# MaTouch_ESP32-S3_2_13_Quad-Color_Eink_V1.net
KiCad netlist of a schematic drawn in EAGLE
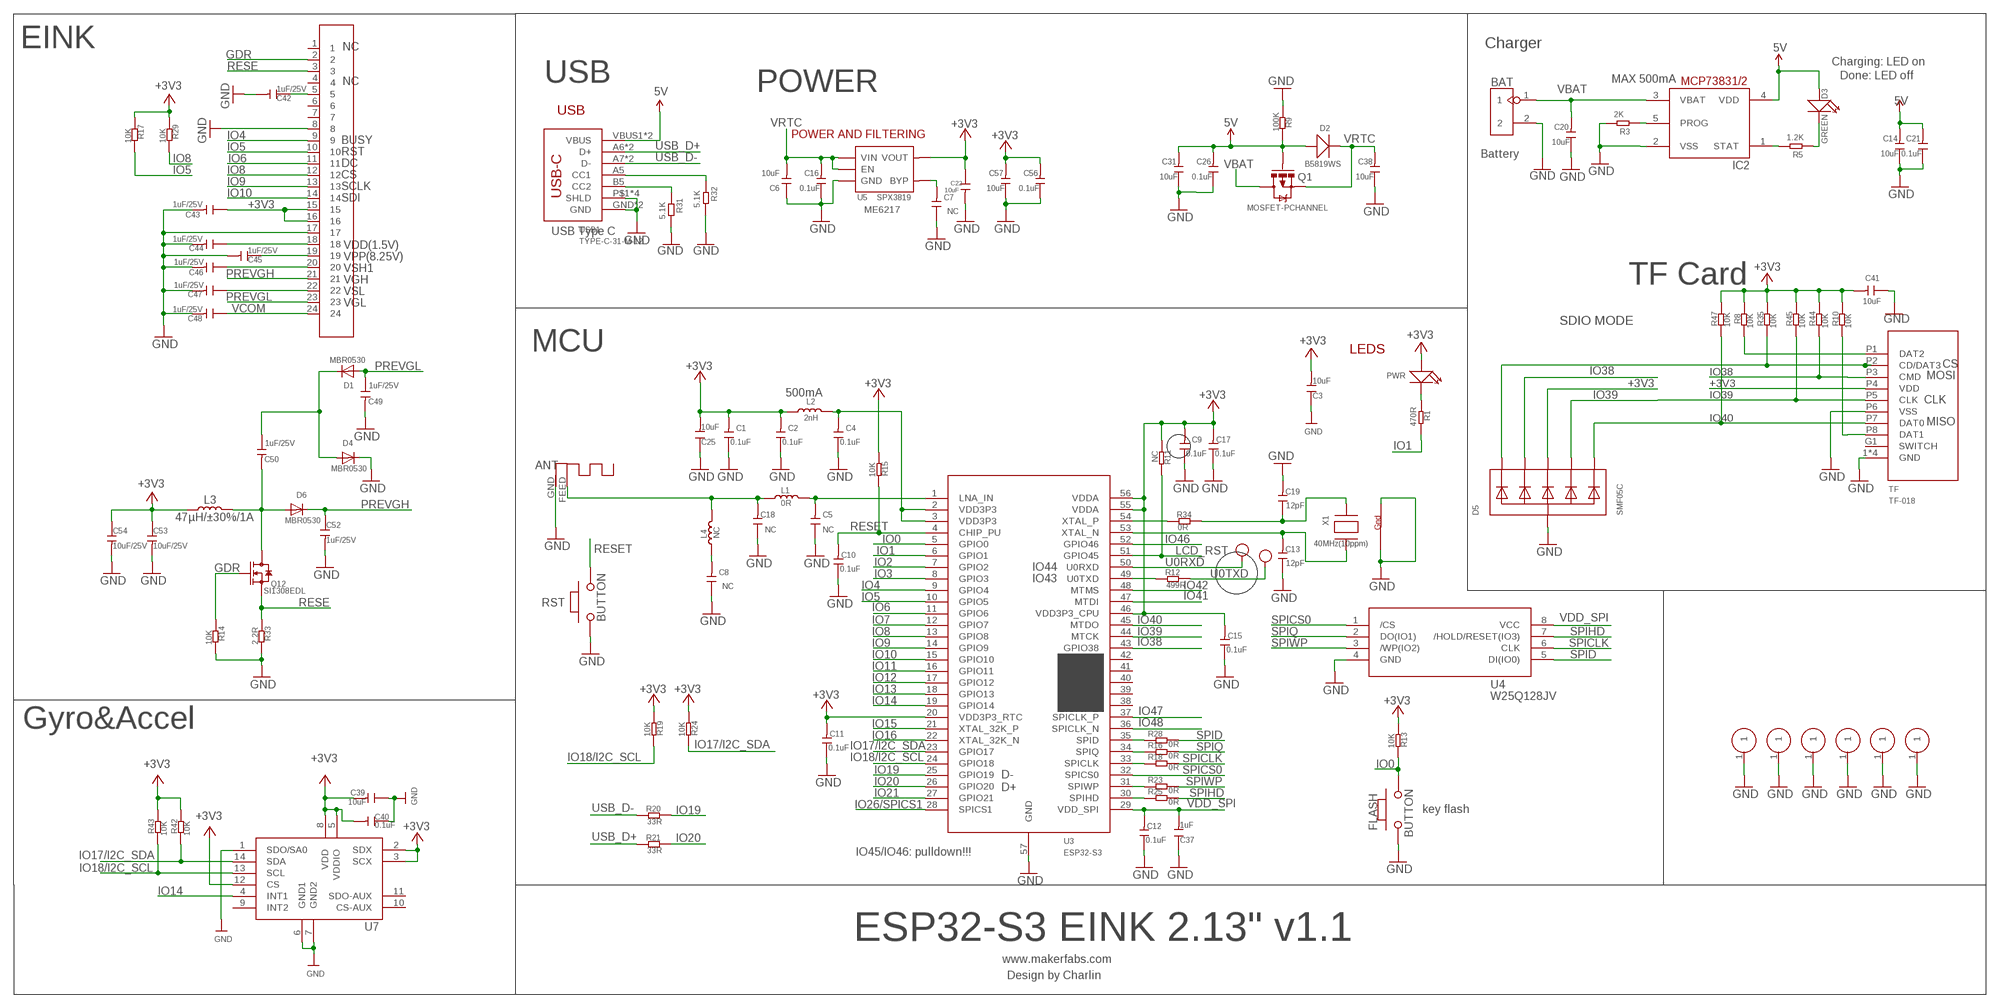
[diagram p0: schematic, sheet 1]

(export (version "E")
  (design (tool "Eeschema 10.0.6"))
  (components
    (comp (ref "ANT1")
      (value "ANTENNA")
      (footprint "eagle-import:RN-ANT")
      (libsource (lib "eagle-import") (part "ANTENNA"))
    )
    (comp (ref "BAT")
      (value "HEADER-2P-2.0")
      (footprint "eagle-import:2P-2.0")
      (libsource (lib "eagle-import") (part "HEADER-2P-2.0"))
    )
    (comp (ref "C1")
      (value "0.1uF")
      (footprint "eagle-import:DISCRETE_C0402")
      (libsource (lib "eagle-import") (part "DISCRETE_C-0402"))
    )
    (comp (ref "C2")
      (value "0.1uF")
      (footprint "eagle-import:DISCRETE_C0402")
      (libsource (lib "eagle-import") (part "DISCRETE_C-0402"))
    )
    (comp (ref "C3")
      (value "10uF")
      (footprint "eagle-import:DISCRETE_C0603")
      (libsource (lib "eagle-import") (part "DISCRETE_C-0603"))
    )
    (comp (ref "C4")
      (value "0.1uF")
      (footprint "eagle-import:DISCRETE_C0402")
      (libsource (lib "eagle-import") (part "DISCRETE_C-0402"))
    )
    (comp (ref "C5")
      (value "NC")
      (footprint "eagle-import:DISCRETE_C0402")
      (libsource (lib "eagle-import") (part "DISCRETE_C-0402"))
    )
    (comp (ref "C6")
      (value "10uF")
      (footprint "eagle-import:DISCRETE_C0603")
      (libsource (lib "eagle-import") (part "DISCRETE_C-0603"))
    )
    (comp (ref "C7")
      (value "NC")
      (footprint "eagle-import:DISCRETE_C0402")
      (libsource (lib "eagle-import") (part "DISCRETE_C-0402"))
    )
    (comp (ref "C8")
      (value "NC")
      (footprint "eagle-import:DISCRETE_C0402")
      (libsource (lib "eagle-import") (part "DISCRETE_C-0402"))
    )
    (comp (ref "C9")
      (value "0.1uF")
      (footprint "eagle-import:DISCRETE_C0402")
      (libsource (lib "eagle-import") (part "DISCRETE_C-0402"))
    )
    (comp (ref "C10")
      (value "0.1uF")
      (footprint "eagle-import:DISCRETE_C0402")
      (libsource (lib "eagle-import") (part "DISCRETE_C-0402"))
    )
    (comp (ref "C11")
      (value "0.1uF")
      (footprint "eagle-import:DISCRETE_C0402")
      (libsource (lib "eagle-import") (part "DISCRETE_C-0402"))
    )
    (comp (ref "C12")
      (value "0.1uF")
      (footprint "eagle-import:DISCRETE_C0402")
      (libsource (lib "eagle-import") (part "DISCRETE_C-0402"))
    )
    (comp (ref "C13")
      (value "12pF")
      (footprint "eagle-import:DISCRETE_C0402")
      (libsource (lib "eagle-import") (part "DISCRETE_C-0402"))
    )
    (comp (ref "C14")
      (value "10uF")
      (footprint "eagle-import:DISCRETE_C0402")
      (libsource (lib "eagle-import") (part "DISCRETE_C-0402"))
    )
    (comp (ref "C15")
      (value "0.1uF")
      (footprint "eagle-import:DISCRETE_C0402")
      (libsource (lib "eagle-import") (part "DISCRETE_C-0402"))
    )
    (comp (ref "C16")
      (value "0.1uF")
      (footprint "eagle-import:DISCRETE_C0402")
      (libsource (lib "eagle-import") (part "DISCRETE_C-0402"))
    )
    (comp (ref "C17")
      (value "0.1uF")
      (footprint "eagle-import:DISCRETE_C0402")
      (libsource (lib "eagle-import") (part "DISCRETE_C-0402"))
    )
    (comp (ref "C18")
      (value "NC")
      (footprint "eagle-import:DISCRETE_C0402")
      (libsource (lib "eagle-import") (part "DISCRETE_C-0402"))
    )
    (comp (ref "C19")
      (value "12pF")
      (footprint "eagle-import:DISCRETE_C0402")
      (libsource (lib "eagle-import") (part "DISCRETE_C-0402"))
    )
    (comp (ref "C20")
      (value "10uF")
      (footprint "eagle-import:DISCRETE_C0402")
      (libsource (lib "eagle-import") (part "DISCRETE_C-0402"))
    )
    (comp (ref "C21")
      (value "0.1uF")
      (footprint "eagle-import:DISCRETE_C0402")
      (libsource (lib "eagle-import") (part "DISCRETE_C-0402"))
    )
    (comp (ref "C22")
      (value "10uF")
      (footprint "eagle-import:0603")
      (libsource (lib "eagle-import") (part "C-0603"))
    )
    (comp (ref "C25")
      (value "10uF")
      (footprint "eagle-import:DISCRETE_C0603")
      (libsource (lib "eagle-import") (part "DISCRETE_C-0603"))
    )
    (comp (ref "C26")
      (value "0.1uF")
      (footprint "eagle-import:DISCRETE_C0402")
      (libsource (lib "eagle-import") (part "DISCRETE_C-0402"))
    )
    (comp (ref "C31")
      (value "10uF")
      (footprint "eagle-import:DISCRETE_C0402")
      (libsource (lib "eagle-import") (part "DISCRETE_C-0402"))
    )
    (comp (ref "C37")
      (value "1uF")
      (footprint "eagle-import:DISCRETE_C0603")
      (libsource (lib "eagle-import") (part "DISCRETE_C-0603"))
    )
    (comp (ref "C38")
      (value "10uF")
      (footprint "eagle-import:DISCRETE_C0402")
      (libsource (lib "eagle-import") (part "DISCRETE_C-0402"))
    )
    (comp (ref "C39")
      (value "10uF")
      (footprint "eagle-import:DISCRETE_C0402")
      (libsource (lib "eagle-import") (part "DISCRETE_C-0402"))
    )
    (comp (ref "C40")
      (value "0.1uF")
      (footprint "eagle-import:DISCRETE_C0402")
      (libsource (lib "eagle-import") (part "DISCRETE_C-0402"))
    )
    (comp (ref "C41")
      (value "10uF")
      (footprint "eagle-import:DISCRETE_C0402")
      (libsource (lib "eagle-import") (part "DISCRETE_C-0402"))
    )
    (comp (ref "C42")
      (value "1uF/25V")
      (footprint "eagle-import:DISCRETE_C0402")
      (libsource (lib "eagle-import") (part "DISCRETE_C-0402"))
    )
    (comp (ref "C43")
      (value "1uF/25V")
      (footprint "eagle-import:DISCRETE_C0402")
      (libsource (lib "eagle-import") (part "DISCRETE_C-0402"))
    )
    (comp (ref "C44")
      (value "1uF/25V")
      (footprint "eagle-import:DISCRETE_C0402")
      (libsource (lib "eagle-import") (part "DISCRETE_C-0402"))
    )
    (comp (ref "C45")
      (value "1uF/25V")
      (footprint "eagle-import:DISCRETE_C0402")
      (libsource (lib "eagle-import") (part "DISCRETE_C-0402"))
    )
    (comp (ref "C46")
      (value "1uF/25V")
      (footprint "eagle-import:DISCRETE_C0402")
      (libsource (lib "eagle-import") (part "DISCRETE_C-0402"))
    )
    (comp (ref "C47")
      (value "1uF/25V")
      (footprint "eagle-import:DISCRETE_C0402")
      (libsource (lib "eagle-import") (part "DISCRETE_C-0402"))
    )
    (comp (ref "C48")
      (value "1uF/25V")
      (footprint "eagle-import:DISCRETE_C0402")
      (libsource (lib "eagle-import") (part "DISCRETE_C-0402"))
    )
    (comp (ref "C49")
      (value "1uF/25V")
      (footprint "eagle-import:DISCRETE_C0402")
      (libsource (lib "eagle-import") (part "DISCRETE_C-0402"))
    )
    (comp (ref "C50")
      (value "1uF/25V")
      (footprint "eagle-import:DISCRETE_C0402")
      (libsource (lib "eagle-import") (part "DISCRETE_C-0402"))
    )
    (comp (ref "C52")
      (value "1uF/25V")
      (footprint "eagle-import:0603")
      (libsource (lib "eagle-import") (part "C-0603"))
    )
    (comp (ref "C53")
      (value "10uF/25V")
      (footprint "eagle-import:0603")
      (libsource (lib "eagle-import") (part "C-0603"))
    )
    (comp (ref "C54")
      (value "10uF/25V")
      (footprint "eagle-import:0603")
      (libsource (lib "eagle-import") (part "C-0603"))
    )
    (comp (ref "C56")
      (value "0.1uF")
      (footprint "eagle-import:DISCRETE_C0402")
      (libsource (lib "eagle-import") (part "DISCRETE_C-0402"))
    )
    (comp (ref "C57")
      (value "10uF")
      (footprint "eagle-import:DISCRETE_C0402")
      (libsource (lib "eagle-import") (part "DISCRETE_C-0402"))
    )
    (comp (ref "D1")
      (value "MBR0530")
      (footprint "eagle-import:SOD-323F")
      (libsource (lib "eagle-import") (part "DIODESOD-323F"))
    )
    (comp (ref "D2")
      (value "B5819WS")
      (footprint "eagle-import:SOD323")
      (libsource (lib "eagle-import") (part "D'0805'"))
    )
    (comp (ref "D3")
      (value "GREEN")
      (footprint "eagle-import:DISCRETE_LED-0603")
      (libsource (lib "eagle-import") (part "DISCRETE_LED0603"))
    )
    (comp (ref "D4")
      (value "MBR0530")
      (footprint "eagle-import:SOD-323F")
      (libsource (lib "eagle-import") (part "DIODESOD-323F"))
    )
    (comp (ref "D5")
      (value "SMF05C")
      (footprint "eagle-import:SOT363")
      (libsource (lib "eagle-import") (part "TVSARRAY_5LANE"))
    )
    (comp (ref "D6")
      (value "MBR0530")
      (footprint "eagle-import:SOD-323F")
      (libsource (lib "eagle-import") (part "DIODESOD-323F"))
    )
    (comp (ref "FLASH")
      (value "BUTTON")
      (footprint "eagle-import:157SW")
      (libsource (lib "eagle-import") (part "PB157"))
    )
    (comp (ref "IC2")
      (value "TP4054")
      (footprint "eagle-import:SOT23-5L")
      (libsource (lib "eagle-import") (part "MCP73831/OT"))
    )
    (comp (ref "J1")
      (value "FPC24-80P-A")
      (footprint "eagle-import:SMD24-80P-1960L440W")
      (libsource (lib "eagle-import") (part "FPC24-80P-A"))
    )
    (comp (ref "L1")
      (value "0R")
      (footprint "eagle-import:DISCRETE_L0402")
      (libsource (lib "eagle-import") (part "DISCRETE_L0402"))
    )
    (comp (ref "L2")
      (value "2nH")
      (footprint "eagle-import:DISCRETE_L0603")
      (libsource (lib "eagle-import") (part "DISCRETE_L0603"))
    )
    (comp (ref "L3")
      (value "47µH/±30%/1A")
      (footprint "eagle-import:CR54")
      (fields (field (name "PROD_ID") "NDUC-10789"))
      (libsource (lib "eagle-import") (part "INDUCTOR-CR54-47UH"))
    )
    (comp (ref "L4")
      (value "NC")
      (footprint "eagle-import:DISCRETE_L0402")
      (libsource (lib "eagle-import") (part "DISCRETE_L0402"))
    )
    (comp (ref "PWR")
      (value "DISCRETE_LED0603")
      (footprint "eagle-import:DISCRETE_LED-0603")
      (libsource (lib "eagle-import") (part "DISCRETE_LED0603"))
    )
    (comp (ref "Q1")
      (value "MOSFET-PCHANNEL")
      (footprint "eagle-import:SOT23-3")
      (libsource (lib "eagle-import") (part "MOSFET-PCHANNEL"))
    )
    (comp (ref "Q12")
      (value "SI1308EDL")
      (footprint "eagle-import:SOT23")
      (libsource (lib "eagle-import") (part "MOSFET-N'SOT23'"))
    )
    (comp (ref "R1")
      (value "470R")
      (footprint "eagle-import:DISCRETE_R0402")
      (libsource (lib "eagle-import") (part "DISCRETE_R-0402"))
    )
    (comp (ref "R3")
      (value "2K")
      (footprint "eagle-import:DISCRETE_R0402")
      (libsource (lib "eagle-import") (part "DISCRETE_R-0402"))
    )
    (comp (ref "R5")
      (value "1.2K")
      (footprint "eagle-import:DISCRETE_R0402")
      (libsource (lib "eagle-import") (part "DISCRETE_R-0402"))
    )
    (comp (ref "R8")
      (value "10K")
      (footprint "eagle-import:DISCRETE_R0402")
      (libsource (lib "eagle-import") (part "DISCRETE_R-0402"))
    )
    (comp (ref "R9")
      (value "100K")
      (footprint "eagle-import:DISCRETE_R0402")
      (libsource (lib "eagle-import") (part "DISCRETE_R-0402"))
    )
    (comp (ref "R10")
      (value "10K")
      (footprint "eagle-import:DISCRETE_R0402")
      (libsource (lib "eagle-import") (part "DISCRETE_R-0402"))
    )
    (comp (ref "R11")
      (value "NC")
      (footprint "eagle-import:DISCRETE_R0402")
      (libsource (lib "eagle-import") (part "DISCRETE_R-0402"))
    )
    (comp (ref "R12")
      (value "499R")
      (footprint "eagle-import:DISCRETE_R0402")
      (libsource (lib "eagle-import") (part "DISCRETE_R-0402"))
    )
    (comp (ref "R13")
      (value "10K")
      (footprint "eagle-import:DISCRETE_R0402")
      (libsource (lib "eagle-import") (part "DISCRETE_R-0402"))
    )
    (comp (ref "R14")
      (value "10K")
      (footprint "eagle-import:DISCRETE_R0402")
      (libsource (lib "eagle-import") (part "DISCRETE_R-0402"))
    )
    (comp (ref "R15")
      (value "10K")
      (footprint "eagle-import:DISCRETE_R0402")
      (libsource (lib "eagle-import") (part "DISCRETE_R-0402"))
    )
    (comp (ref "R16")
      (value "0R")
      (footprint "eagle-import:DISCRETE_R0402")
      (libsource (lib "eagle-import") (part "DISCRETE_R-0402"))
    )
    (comp (ref "R17")
      (value "10K")
      (footprint "eagle-import:DISCRETE_R0402")
      (libsource (lib "eagle-import") (part "DISCRETE_R-0402"))
    )
    (comp (ref "R18")
      (value "0R")
      (footprint "eagle-import:DISCRETE_R0402")
      (libsource (lib "eagle-import") (part "DISCRETE_R-0402"))
    )
    (comp (ref "R19")
      (value "10K")
      (footprint "eagle-import:DISCRETE_R0402")
      (libsource (lib "eagle-import") (part "DISCRETE_R-0402"))
    )
    (comp (ref "R20")
      (value "33R")
      (footprint "eagle-import:DISCRETE_R0402")
      (libsource (lib "eagle-import") (part "DISCRETE_R-0402"))
    )
    (comp (ref "R21")
      (value "33R")
      (footprint "eagle-import:DISCRETE_R0402")
      (libsource (lib "eagle-import") (part "DISCRETE_R-0402"))
    )
    (comp (ref "R23")
      (value "0R")
      (footprint "eagle-import:DISCRETE_R0402")
      (libsource (lib "eagle-import") (part "DISCRETE_R-0402"))
    )
    (comp (ref "R24")
      (value "10K")
      (footprint "eagle-import:DISCRETE_R0402")
      (libsource (lib "eagle-import") (part "DISCRETE_R-0402"))
    )
    (comp (ref "R25")
      (value "0R")
      (footprint "eagle-import:DISCRETE_R0402")
      (libsource (lib "eagle-import") (part "DISCRETE_R-0402"))
    )
    (comp (ref "R28")
      (value "0R")
      (footprint "eagle-import:DISCRETE_R0402")
      (libsource (lib "eagle-import") (part "DISCRETE_R-0402"))
    )
    (comp (ref "R29")
      (value "10K")
      (footprint "eagle-import:DISCRETE_R0402")
      (libsource (lib "eagle-import") (part "DISCRETE_R-0402"))
    )
    (comp (ref "R31")
      (value "5.1K")
      (footprint "eagle-import:DISCRETE_R0402")
      (libsource (lib "eagle-import") (part "DISCRETE_R-0402"))
    )
    (comp (ref "R32")
      (value "5.1K")
      (footprint "eagle-import:DISCRETE_R0402")
      (libsource (lib "eagle-import") (part "DISCRETE_R-0402"))
    )
    (comp (ref "R33")
      (value "2.2R")
      (footprint "eagle-import:DISCRETE_R0402")
      (libsource (lib "eagle-import") (part "DISCRETE_R-0402"))
    )
    (comp (ref "R34")
      (value "0R")
      (footprint "eagle-import:DISCRETE_R0402")
      (libsource (lib "eagle-import") (part "DISCRETE_R-0402"))
    )
    (comp (ref "R35")
      (value "10K")
      (footprint "eagle-import:DISCRETE_R0402")
      (libsource (lib "eagle-import") (part "DISCRETE_R-0402"))
    )
    (comp (ref "R42")
      (value "10K")
      (footprint "eagle-import:DISCRETE_R0402")
      (libsource (lib "eagle-import") (part "DISCRETE_R-0402"))
    )
    (comp (ref "R43")
      (value "10K")
      (footprint "eagle-import:DISCRETE_R0402")
      (libsource (lib "eagle-import") (part "DISCRETE_R-0402"))
    )
    (comp (ref "R44")
      (value "10K")
      (footprint "eagle-import:DISCRETE_R0402")
      (libsource (lib "eagle-import") (part "DISCRETE_R-0402"))
    )
    (comp (ref "R45")
      (value "10K")
      (footprint "eagle-import:DISCRETE_R0402")
      (libsource (lib "eagle-import") (part "DISCRETE_R-0402"))
    )
    (comp (ref "R47")
      (value "10K")
      (footprint "eagle-import:DISCRETE_R0402")
      (libsource (lib "eagle-import") (part "DISCRETE_R-0402"))
    )
    (comp (ref "RST")
      (value "BUTTON")
      (footprint "eagle-import:157SW")
      (libsource (lib "eagle-import") (part "PB157"))
    )
    (comp (ref "RX")
      (value "TEST-POINT'4545'")
      (footprint "eagle-import:TP-D45MIL")
      (fields (field (name "PARTNO") "DNP") (field (name "PARTNO_1") "DNP"))
      (libsource (lib "eagle-import") (part "TEST-POINT'4545'"))
    )
    (comp (ref "S1")
      (value "ONEPIN01")
      (footprint "eagle-import:ONEPIN01")
      (libsource (lib "eagle-import") (part "ONEPIN01"))
    )
    (comp (ref "S2")
      (value "ONEPIN01")
      (footprint "eagle-import:ONEPIN01")
      (libsource (lib "eagle-import") (part "ONEPIN01"))
    )
    (comp (ref "S3")
      (value "ONEPIN01")
      (footprint "eagle-import:ONEPIN01")
      (libsource (lib "eagle-import") (part "ONEPIN01"))
    )
    (comp (ref "S4")
      (value "ONEPIN01")
      (footprint "eagle-import:ONEPIN01")
      (libsource (lib "eagle-import") (part "ONEPIN01"))
    )
    (comp (ref "S5")
      (value "ONEPIN01")
      (footprint "eagle-import:ONEPIN01")
      (libsource (lib "eagle-import") (part "ONEPIN01"))
    )
    (comp (ref "S6")
      (value "ONEPIN01")
      (footprint "eagle-import:ONEPIN01")
      (libsource (lib "eagle-import") (part "ONEPIN01"))
    )
    (comp (ref "TF")
      (value "TF-018")
      (footprint "eagle-import:TF-018")
      (libsource (lib "eagle-import") (part "TF-018"))
    )
    (comp (ref "TX")
      (value "TEST-POINT'4545'")
      (footprint "eagle-import:TP-D45MIL")
      (fields (field (name "PARTNO") "DNP") (field (name "PARTNO_1") "DNP"))
      (libsource (lib "eagle-import") (part "TEST-POINT'4545'"))
    )
    (comp (ref "U3")
      (value "ESP32-S3")
      (footprint "eagle-import:QFN56-7_7MM")
      (libsource (lib "eagle-import") (part "ESP32-S3"))
    )
    (comp (ref "U4")
      (value "W25Q128JV")
      (footprint "eagle-import:SOIC-8-208MIL")
      (libsource (lib "eagle-import") (part "W25Q128JV"))
    )
    (comp (ref "U5")
      (value "SPX3819")
      (footprint "eagle-import:SOT23-5")
      (libsource (lib "eagle-import") (part "SPX3819"))
    )
    (comp (ref "U7")
      (value "QMI8658A")
      (footprint "eagle-import:LGA14-50P-300L250W86H")
      (libsource (lib "eagle-import") (part "QMI8658A"))
    )
    (comp (ref "USB1")
      (value "TYPE-C-31-M-12")
      (footprint "eagle-import:TYPE-C-31-M-12")
      (libsource (lib "eagle-import") (part "TYPE-C-31-M-12"))
    )
    (comp (ref "X1")
      (value "40MHz(10ppm)")
      (footprint "eagle-import:NX3225")
      (libsource (lib "eagle-import") (part "XTAL-4-3225"))
    )
  )
  (nets
    (net (code "1") (name "+3V3") (class "Default")
      (node (ref "C1") (pin "2") (pinfunction "2_2") (pintype "passive"))
      (node (ref "C11") (pin "2") (pinfunction "2_2") (pintype "passive"))
      (node (ref "C15") (pin "2") (pinfunction "2_2") (pintype "passive"))
      (node (ref "C17") (pin "2") (pinfunction "2_2") (pintype "passive"))
      (node (ref "C2") (pin "2") (pinfunction "2_2") (pintype "passive"))
      (node (ref "C22") (pin "1") (pinfunction "1_1") (pintype "passive"))
      (node (ref "C25") (pin "2") (pinfunction "2_2") (pintype "passive"))
      (node (ref "C3") (pin "2") (pinfunction "2_2") (pintype "passive"))
      (node (ref "C39") (pin "2") (pinfunction "2_2") (pintype "passive"))
      (node (ref "C40") (pin "2") (pinfunction "2_2") (pintype "passive"))
      (node (ref "C41") (pin "2") (pinfunction "2_2") (pintype "passive"))
      (node (ref "C43") (pin "1") (pinfunction "1_1") (pintype "passive"))
      (node (ref "C53") (pin "1") (pinfunction "1_1") (pintype "passive"))
      (node (ref "C54") (pin "1") (pinfunction "1_1") (pintype "passive"))
      (node (ref "C56") (pin "2") (pinfunction "2_2") (pintype "passive"))
      (node (ref "C57") (pin "2") (pinfunction "2_2") (pintype "passive"))
      (node (ref "C9") (pin "2") (pinfunction "2_2") (pintype "passive"))
      (node (ref "D5") (pin "4") (pinfunction "C3_4") (pintype "passive"))
      (node (ref "J1") (pin "15") (pinfunction "15_15") (pintype "bidirectional"))
      (node (ref "J1") (pin "16") (pinfunction "16_16") (pintype "bidirectional"))
      (node (ref "L2") (pin "1") (pinfunction "1_1") (pintype "passive"))
      (node (ref "L3") (pin "P$1") (pinfunction "1_P$1") (pintype "passive"))
      (node (ref "PWR") (pin "+") (pinfunction "+_+") (pintype "passive"))
      (node (ref "R10") (pin "2") (pinfunction "2_2") (pintype "passive"))
      (node (ref "R11") (pin "2") (pinfunction "2_2") (pintype "passive"))
      (node (ref "R13") (pin "2") (pinfunction "2_2") (pintype "passive"))
      (node (ref "R15") (pin "2") (pinfunction "2_2") (pintype "passive"))
      (node (ref "R17") (pin "1") (pinfunction "1_1") (pintype "passive"))
      (node (ref "R19") (pin "2") (pinfunction "2_2") (pintype "passive"))
      (node (ref "R24") (pin "2") (pinfunction "2_2") (pintype "passive"))
      (node (ref "R29") (pin "1") (pinfunction "1_1") (pintype "passive"))
      (node (ref "R35") (pin "2") (pinfunction "2_2") (pintype "passive"))
      (node (ref "R42") (pin "2") (pinfunction "2_2") (pintype "passive"))
      (node (ref "R43") (pin "2") (pinfunction "2_2") (pintype "passive"))
      (node (ref "R44") (pin "2") (pinfunction "2_2") (pintype "passive"))
      (node (ref "R45") (pin "2") (pinfunction "2_2") (pintype "passive"))
      (node (ref "R47") (pin "2") (pinfunction "2_2") (pintype "passive"))
      (node (ref "R8") (pin "2") (pinfunction "2_2") (pintype "passive"))
      (node (ref "TF") (pin "P4") (pinfunction "VDD_P4") (pintype "bidirectional"))
      (node (ref "U3") (pin "20") (pinfunction "VDD3P3_RTC_20") (pintype "bidirectional"))
      (node (ref "U3") (pin "46") (pinfunction "VDD3P3_CPU_46") (pintype "bidirectional"))
      (node (ref "U3") (pin "55") (pinfunction "VDDA_55") (pintype "bidirectional"))
      (node (ref "U3") (pin "56") (pinfunction "VDDA_56") (pintype "bidirectional"))
      (node (ref "U5") (pin "5") (pinfunction "VOUT_5") (pintype "bidirectional"))
      (node (ref "U7") (pin "12") (pinfunction "CS_12") (pintype "bidirectional"))
      (node (ref "U7") (pin "2") (pinfunction "SDX_2") (pintype "bidirectional"))
      (node (ref "U7") (pin "3") (pinfunction "SCX_3") (pintype "bidirectional"))
      (node (ref "U7") (pin "5") (pinfunction "VDDIO_5") (pintype "bidirectional"))
      (node (ref "U7") (pin "8") (pinfunction "VDD_8") (pintype "bidirectional"))
    )
    (net (code "2") (name "/GDR") (class "Default")
      (node (ref "J1") (pin "2") (pinfunction "2_2") (pintype "bidirectional"))
      (node (ref "Q12") (pin "1") (pinfunction "G_1") (pintype "passive"))
      (node (ref "R14") (pin "1") (pinfunction "1_1") (pintype "passive"))
    )
    (net (code "3") (name "/IO0") (class "Default")
      (node (ref "FLASH") (pin "2") (pinfunction "2_2") (pintype "passive"))
      (node (ref "R13") (pin "1") (pinfunction "1_1") (pintype "passive"))
      (node (ref "U3") (pin "5") (pinfunction "GPIO0_5") (pintype "bidirectional"))
    )
    (net (code "4") (name "/IO1") (class "Default")
      (node (ref "R1") (pin "1") (pinfunction "1_1") (pintype "passive"))
      (node (ref "U3") (pin "6") (pinfunction "GPIO1_6") (pintype "bidirectional"))
    )
    (net (code "5") (name "/IO2") (class "Default")
      (node (ref "U3") (pin "7") (pinfunction "GPIO2_7") (pintype "bidirectional"))
    )
    (net (code "6") (name "/IO3") (class "Default")
      (node (ref "U3") (pin "8") (pinfunction "GPIO3_8") (pintype "bidirectional"))
    )
    (net (code "7") (name "/IO4") (class "Default")
      (node (ref "J1") (pin "9") (pinfunction "9_9") (pintype "bidirectional"))
      (node (ref "U3") (pin "9") (pinfunction "GPIO4_9") (pintype "bidirectional"))
    )
    (net (code "8") (name "/IO5") (class "Default")
      (node (ref "J1") (pin "10") (pinfunction "10_10") (pintype "bidirectional"))
      (node (ref "R17") (pin "2") (pinfunction "2_2") (pintype "passive"))
      (node (ref "U3") (pin "10") (pinfunction "GPIO5_10") (pintype "bidirectional"))
    )
    (net (code "9") (name "/IO6") (class "Default")
      (node (ref "J1") (pin "11") (pinfunction "11_11") (pintype "bidirectional"))
      (node (ref "U3") (pin "11") (pinfunction "GPIO6_11") (pintype "bidirectional"))
    )
    (net (code "10") (name "/IO7") (class "Default")
      (node (ref "U3") (pin "12") (pinfunction "GPIO7_12") (pintype "bidirectional"))
    )
    (net (code "11") (name "/IO8") (class "Default")
      (node (ref "J1") (pin "12") (pinfunction "12_12") (pintype "bidirectional"))
      (node (ref "R29") (pin "2") (pinfunction "2_2") (pintype "passive"))
      (node (ref "U3") (pin "13") (pinfunction "GPIO8_13") (pintype "bidirectional"))
    )
    (net (code "12") (name "/IO9") (class "Default")
      (node (ref "J1") (pin "13") (pinfunction "13_13") (pintype "bidirectional"))
      (node (ref "U3") (pin "14") (pinfunction "GPIO9_14") (pintype "bidirectional"))
    )
    (net (code "13") (name "/IO10") (class "Default")
      (node (ref "J1") (pin "14") (pinfunction "14_14") (pintype "bidirectional"))
      (node (ref "U3") (pin "15") (pinfunction "GPIO10_15") (pintype "bidirectional"))
    )
    (net (code "14") (name "/IO11") (class "Default")
      (node (ref "U3") (pin "16") (pinfunction "GPIO11_16") (pintype "bidirectional"))
    )
    (net (code "15") (name "/IO12") (class "Default")
      (node (ref "U3") (pin "17") (pinfunction "GPIO12_17") (pintype "bidirectional"))
    )
    (net (code "16") (name "/IO13") (class "Default")
      (node (ref "U3") (pin "18") (pinfunction "GPIO13_18") (pintype "bidirectional"))
    )
    (net (code "17") (name "/IO14") (class "Default")
      (node (ref "U3") (pin "19") (pinfunction "GPIO14_19") (pintype "bidirectional"))
      (node (ref "U7") (pin "4") (pinfunction "INT1_4") (pintype "bidirectional"))
    )
    (net (code "18") (name "/IO15") (class "Default")
      (node (ref "U3") (pin "21") (pinfunction "XTAL_32K_P_21") (pintype "bidirectional"))
    )
    (net (code "19") (name "/IO16") (class "Default")
      (node (ref "U3") (pin "22") (pinfunction "XTAL_32K_N_22") (pintype "bidirectional"))
    )
    (net (code "20") (name "/IO17{slash}I2C_SDA") (class "Default")
      (node (ref "R24") (pin "1") (pinfunction "1_1") (pintype "passive"))
      (node (ref "R42") (pin "1") (pinfunction "1_1") (pintype "passive"))
      (node (ref "U3") (pin "23") (pinfunction "GPIO17_23") (pintype "bidirectional"))
      (node (ref "U7") (pin "14") (pinfunction "SDA_14") (pintype "bidirectional"))
    )
    (net (code "21") (name "/IO18{slash}I2C_SCL") (class "Default")
      (node (ref "R19") (pin "1") (pinfunction "1_1") (pintype "passive"))
      (node (ref "R43") (pin "1") (pinfunction "1_1") (pintype "passive"))
      (node (ref "U3") (pin "24") (pinfunction "GPIO18_24") (pintype "bidirectional"))
      (node (ref "U7") (pin "13") (pinfunction "SCL_13") (pintype "bidirectional"))
    )
    (net (code "22") (name "/IO19") (class "Default")
      (node (ref "R20") (pin "1") (pinfunction "1_1") (pintype "passive"))
      (node (ref "U3") (pin "25") (pinfunction "GPIO19_25") (pintype "bidirectional"))
    )
    (net (code "23") (name "/IO20") (class "Default")
      (node (ref "R21") (pin "1") (pinfunction "1_1") (pintype "passive"))
      (node (ref "U3") (pin "26") (pinfunction "GPIO20_26") (pintype "bidirectional"))
    )
    (net (code "24") (name "/IO21") (class "Default")
      (node (ref "U3") (pin "27") (pinfunction "GPIO21_27") (pintype "bidirectional"))
    )
    (net (code "25") (name "/IO26{slash}SPICS1") (class "Default")
      (node (ref "U3") (pin "28") (pinfunction "SPICS1_28") (pintype "bidirectional"))
    )
    (net (code "26") (name "/IO38") (class "Default")
      (node (ref "D5") (pin "3") (pinfunction "C2_3") (pintype "passive"))
      (node (ref "R44") (pin "1") (pinfunction "1_1") (pintype "passive"))
      (node (ref "TF") (pin "P3") (pinfunction "CMD_P3") (pintype "bidirectional"))
      (node (ref "U3") (pin "43") (pinfunction "GPIO38_43") (pintype "bidirectional"))
    )
    (net (code "27") (name "/IO39") (class "Default")
      (node (ref "D5") (pin "5") (pinfunction "C4_5") (pintype "passive"))
      (node (ref "R45") (pin "1") (pinfunction "1_1") (pintype "passive"))
      (node (ref "TF") (pin "P5") (pinfunction "CLK_P5") (pintype "bidirectional"))
      (node (ref "U3") (pin "44") (pinfunction "MTCK_44") (pintype "bidirectional"))
    )
    (net (code "28") (name "/IO40") (class "Default")
      (node (ref "D5") (pin "6") (pinfunction "C5_6") (pintype "passive"))
      (node (ref "R47") (pin "1") (pinfunction "1_1") (pintype "passive"))
      (node (ref "TF") (pin "P7") (pinfunction "DAT0_P7") (pintype "bidirectional"))
      (node (ref "U3") (pin "45") (pinfunction "MTDO_45") (pintype "bidirectional"))
    )
    (net (code "29") (name "/IO41") (class "Default")
      (node (ref "U3") (pin "47") (pinfunction "MTDI_47") (pintype "bidirectional"))
    )
    (net (code "30") (name "/IO42") (class "Default")
      (node (ref "U3") (pin "48") (pinfunction "MTMS_48") (pintype "bidirectional"))
    )
    (net (code "31") (name "/IO46") (class "Default")
      (node (ref "U3") (pin "52") (pinfunction "GPIO46_52") (pintype "bidirectional"))
    )
    (net (code "32") (name "/IO47") (class "Default")
      (node (ref "U3") (pin "37") (pinfunction "SPICLK_P_37") (pintype "bidirectional"))
    )
    (net (code "33") (name "/IO48") (class "Default")
      (node (ref "U3") (pin "36") (pinfunction "SPICLK_N_36") (pintype "bidirectional"))
    )
    (net (code "34") (name "/LCD_RST") (class "Default")
      (node (ref "R11") (pin "1") (pinfunction "1_1") (pintype "passive"))
      (node (ref "U3") (pin "51") (pinfunction "GPIO45_51") (pintype "bidirectional"))
    )
    (net (code "35") (name "/PREVGH") (class "Default")
      (node (ref "C52") (pin "1") (pinfunction "1_1") (pintype "passive"))
      (node (ref "D6") (pin "C") (pinfunction "C_C") (pintype "passive"))
      (node (ref "J1") (pin "21") (pinfunction "21_21") (pintype "bidirectional"))
    )
    (net (code "36") (name "/PREVGL") (class "Default")
      (node (ref "C49") (pin "1") (pinfunction "1_1") (pintype "passive"))
      (node (ref "D1") (pin "A") (pinfunction "A_A") (pintype "passive"))
      (node (ref "J1") (pin "23") (pinfunction "23_23") (pintype "bidirectional"))
    )
    (net (code "37") (name "/RESE") (class "Default")
      (node (ref "J1") (pin "3") (pinfunction "3_3") (pintype "bidirectional"))
      (node (ref "Q12") (pin "2") (pinfunction "S_2") (pintype "passive"))
      (node (ref "R33") (pin "1") (pinfunction "1_1") (pintype "passive"))
    )
    (net (code "38") (name "/RESET") (class "Default")
      (node (ref "C10") (pin "2") (pinfunction "2_2") (pintype "passive"))
      (node (ref "R15") (pin "1") (pinfunction "1_1") (pintype "passive"))
      (node (ref "RST") (pin "2") (pinfunction "2_2") (pintype "passive"))
      (node (ref "U3") (pin "4") (pinfunction "CHIP_PU_4") (pintype "bidirectional"))
    )
    (net (code "39") (name "/SPICLK") (class "Default")
      (node (ref "R18") (pin "1") (pinfunction "1_1") (pintype "passive"))
      (node (ref "U4") (pin "6") (pinfunction "CLK_6") (pintype "bidirectional"))
    )
    (net (code "40") (name "/SPICS0") (class "Default")
      (node (ref "U3") (pin "32") (pinfunction "SPICS0_32") (pintype "bidirectional"))
      (node (ref "U4") (pin "1") (pinfunction "/CS_1") (pintype "bidirectional"))
    )
    (net (code "41") (name "/SPID") (class "Default")
      (node (ref "R28") (pin "1") (pinfunction "1_1") (pintype "passive"))
      (node (ref "U4") (pin "5") (pinfunction "DI(IO0)_5") (pintype "bidirectional"))
    )
    (net (code "42") (name "/SPIHD") (class "Default")
      (node (ref "R25") (pin "1") (pinfunction "1_1") (pintype "passive"))
      (node (ref "U4") (pin "7") (pinfunction "/HOLD/RESET(IO3)_7") (pintype "bidirectional"))
    )
    (net (code "43") (name "/SPIQ") (class "Default")
      (node (ref "R16") (pin "1") (pinfunction "1_1") (pintype "passive"))
      (node (ref "U4") (pin "2") (pinfunction "DO(IO1)_2") (pintype "bidirectional"))
    )
    (net (code "44") (name "/SPIWP") (class "Default")
      (node (ref "R23") (pin "1") (pinfunction "1_1") (pintype "passive"))
      (node (ref "U4") (pin "3") (pinfunction "/WP(IO2)_3") (pintype "bidirectional"))
    )
    (net (code "45") (name "/U0RXD") (class "Default")
      (node (ref "RX") (pin "T") (pinfunction "T_T") (pintype "bidirectional"))
      (node (ref "U3") (pin "50") (pinfunction "U0RXD_50") (pintype "bidirectional"))
    )
    (net (code "46") (name "/U0TXD") (class "Default")
      (node (ref "R12") (pin "1") (pinfunction "1_1") (pintype "passive"))
      (node (ref "TX") (pin "T") (pinfunction "T_T") (pintype "bidirectional"))
    )
    (net (code "47") (name "/USB_D+") (class "Default")
      (node (ref "R21") (pin "2") (pinfunction "2_2") (pintype "passive"))
      (node (ref "USB1") (pin "A6") (pinfunction "D+_A6") (pintype "bidirectional"))
      (node (ref "USB1") (pin "B6") (pinfunction "D+_B6") (pintype "bidirectional"))
    )
    (net (code "48") (name "/USB_D-") (class "Default")
      (node (ref "R20") (pin "2") (pinfunction "2_2") (pintype "passive"))
      (node (ref "USB1") (pin "A7") (pinfunction "D-_A7") (pintype "bidirectional"))
      (node (ref "USB1") (pin "B7") (pinfunction "D-_B7") (pintype "bidirectional"))
    )
    (net (code "49") (name "/VBAT") (class "Default")
      (node (ref "BAT") (pin "1") (pinfunction "1_1") (pintype "bidirectional"))
      (node (ref "C20") (pin "2") (pinfunction "2_2") (pintype "passive"))
      (node (ref "IC2") (pin "3") (pinfunction "VBAT_3") (pintype "bidirectional"))
      (node (ref "Q1") (pin "3") (pinfunction "D_3") (pintype "passive"))
    )
    (net (code "50") (name "/VCOM") (class "Default")
      (node (ref "C48") (pin "1") (pinfunction "1_1") (pintype "passive"))
      (node (ref "J1") (pin "24") (pinfunction "24_24") (pintype "bidirectional"))
    )
    (net (code "51") (name "/VDD_SPI") (class "Default")
      (node (ref "C12") (pin "2") (pinfunction "2_2") (pintype "passive"))
      (node (ref "C37") (pin "2") (pinfunction "2_2") (pintype "passive"))
      (node (ref "U3") (pin "29") (pinfunction "VDD_SPI_29") (pintype "bidirectional"))
      (node (ref "U4") (pin "8") (pinfunction "VCC_8") (pintype "bidirectional"))
    )
    (net (code "52") (name "/VRTC") (class "Default")
      (node (ref "C16") (pin "2") (pinfunction "2_2") (pintype "passive"))
      (node (ref "C38") (pin "2") (pinfunction "2_2") (pintype "passive"))
      (node (ref "C6") (pin "2") (pinfunction "2_2") (pintype "passive"))
      (node (ref "D2") (pin "-") (pinfunction "-_-") (pintype "passive"))
      (node (ref "Q1") (pin "2") (pinfunction "S_2") (pintype "passive"))
      (node (ref "U5") (pin "1") (pinfunction "VIN_1") (pintype "bidirectional"))
      (node (ref "U5") (pin "3") (pinfunction "EN_3") (pintype "bidirectional"))
    )
    (net (code "53") (name "5V") (class "Default")
      (node (ref "C14") (pin "2") (pinfunction "2_2") (pintype "passive"))
      (node (ref "C21") (pin "2") (pinfunction "2_2") (pintype "passive"))
      (node (ref "C26") (pin "2") (pinfunction "2_2") (pintype "passive"))
      (node (ref "C31") (pin "2") (pinfunction "2_2") (pintype "passive"))
      (node (ref "D2") (pin "+") (pinfunction "+_+") (pintype "passive"))
      (node (ref "D3") (pin "+") (pinfunction "+_+") (pintype "passive"))
      (node (ref "IC2") (pin "4") (pinfunction "VDD_4") (pintype "power_in"))
      (node (ref "Q1") (pin "1") (pinfunction "G_1") (pintype "passive"))
      (node (ref "R9") (pin "2") (pinfunction "2_2") (pintype "passive"))
      (node (ref "USB1") (pin "VBUS1") (pinfunction "VBUS_VBUS1") (pintype "bidirectional"))
      (node (ref "USB1") (pin "VBUS2") (pinfunction "VBUS_VBUS2") (pintype "bidirectional"))
    )
    (net (code "54") (name "GND") (class "Default")
      (node (ref "ANT1") (pin "GND") (pinfunction "GND_GND") (pintype "passive"))
      (node (ref "BAT") (pin "2") (pinfunction "2_2") (pintype "bidirectional"))
      (node (ref "C1") (pin "1") (pinfunction "1_1") (pintype "passive"))
      (node (ref "C10") (pin "1") (pinfunction "1_1") (pintype "passive"))
      (node (ref "C11") (pin "1") (pinfunction "1_1") (pintype "passive"))
      (node (ref "C12") (pin "1") (pinfunction "1_1") (pintype "passive"))
      (node (ref "C13") (pin "1") (pinfunction "1_1") (pintype "passive"))
      (node (ref "C14") (pin "1") (pinfunction "1_1") (pintype "passive"))
      (node (ref "C15") (pin "1") (pinfunction "1_1") (pintype "passive"))
      (node (ref "C16") (pin "1") (pinfunction "1_1") (pintype "passive"))
      (node (ref "C17") (pin "1") (pinfunction "1_1") (pintype "passive"))
      (node (ref "C18") (pin "1") (pinfunction "1_1") (pintype "passive"))
      (node (ref "C19") (pin "2") (pinfunction "2_2") (pintype "passive"))
      (node (ref "C2") (pin "1") (pinfunction "1_1") (pintype "passive"))
      (node (ref "C20") (pin "1") (pinfunction "1_1") (pintype "passive"))
      (node (ref "C21") (pin "1") (pinfunction "1_1") (pintype "passive"))
      (node (ref "C22") (pin "2") (pinfunction "2_2") (pintype "passive"))
      (node (ref "C25") (pin "1") (pinfunction "1_1") (pintype "passive"))
      (node (ref "C26") (pin "1") (pinfunction "1_1") (pintype "passive"))
      (node (ref "C3") (pin "1") (pinfunction "1_1") (pintype "passive"))
      (node (ref "C31") (pin "1") (pinfunction "1_1") (pintype "passive"))
      (node (ref "C37") (pin "1") (pinfunction "1_1") (pintype "passive"))
      (node (ref "C38") (pin "1") (pinfunction "1_1") (pintype "passive"))
      (node (ref "C39") (pin "1") (pinfunction "1_1") (pintype "passive"))
      (node (ref "C4") (pin "1") (pinfunction "1_1") (pintype "passive"))
      (node (ref "C40") (pin "1") (pinfunction "1_1") (pintype "passive"))
      (node (ref "C41") (pin "1") (pinfunction "1_1") (pintype "passive"))
      (node (ref "C42") (pin "2") (pinfunction "2_2") (pintype "passive"))
      (node (ref "C43") (pin "2") (pinfunction "2_2") (pintype "passive"))
      (node (ref "C44") (pin "2") (pinfunction "2_2") (pintype "passive"))
      (node (ref "C45") (pin "2") (pinfunction "2_2") (pintype "passive"))
      (node (ref "C46") (pin "2") (pinfunction "2_2") (pintype "passive"))
      (node (ref "C47") (pin "2") (pinfunction "2_2") (pintype "passive"))
      (node (ref "C48") (pin "2") (pinfunction "2_2") (pintype "passive"))
      (node (ref "C49") (pin "2") (pinfunction "2_2") (pintype "passive"))
      (node (ref "C5") (pin "1") (pinfunction "1_1") (pintype "passive"))
      (node (ref "C52") (pin "2") (pinfunction "2_2") (pintype "passive"))
      (node (ref "C53") (pin "2") (pinfunction "2_2") (pintype "passive"))
      (node (ref "C54") (pin "2") (pinfunction "2_2") (pintype "passive"))
      (node (ref "C56") (pin "1") (pinfunction "1_1") (pintype "passive"))
      (node (ref "C57") (pin "1") (pinfunction "1_1") (pintype "passive"))
      (node (ref "C6") (pin "1") (pinfunction "1_1") (pintype "passive"))
      (node (ref "C7") (pin "1") (pinfunction "1_1") (pintype "passive"))
      (node (ref "C8") (pin "1") (pinfunction "1_1") (pintype "passive"))
      (node (ref "C9") (pin "1") (pinfunction "1_1") (pintype "passive"))
      (node (ref "D4") (pin "C") (pinfunction "C_C") (pintype "passive"))
      (node (ref "D5") (pin "2") (pinfunction "A_2") (pintype "passive"))
      (node (ref "FLASH") (pin "1") (pinfunction "1_1") (pintype "passive"))
      (node (ref "IC2") (pin "2") (pinfunction "VSS_2") (pintype "power_in"))
      (node (ref "J1") (pin "17") (pinfunction "17_17") (pintype "bidirectional"))
      (node (ref "J1") (pin "8") (pinfunction "8_8") (pintype "bidirectional"))
      (node (ref "R14") (pin "2") (pinfunction "2_2") (pintype "passive"))
      (node (ref "R3") (pin "2") (pinfunction "2_2") (pintype "passive"))
      (node (ref "R31") (pin "2") (pinfunction "2_2") (pintype "passive"))
      (node (ref "R32") (pin "2") (pinfunction "2_2") (pintype "passive"))
      (node (ref "R33") (pin "2") (pinfunction "2_2") (pintype "passive"))
      (node (ref "R9") (pin "1") (pinfunction "1_1") (pintype "passive"))
      (node (ref "RST") (pin "1") (pinfunction "1_1") (pintype "passive"))
      (node (ref "S1") (pin "1") (pinfunction "1_1") (pintype "bidirectional"))
      (node (ref "S2") (pin "1") (pinfunction "1_1") (pintype "bidirectional"))
      (node (ref "S3") (pin "1") (pinfunction "1_1") (pintype "bidirectional"))
      (node (ref "S4") (pin "1") (pinfunction "1_1") (pintype "bidirectional"))
      (node (ref "S5") (pin "1") (pinfunction "1_1") (pintype "bidirectional"))
      (node (ref "S6") (pin "1") (pinfunction "1_1") (pintype "bidirectional"))
      (node (ref "TF") (pin "1") (pinfunction "GND_1") (pintype "bidirectional"))
      (node (ref "TF") (pin "2") (pinfunction "GND_2") (pintype "bidirectional"))
      (node (ref "TF") (pin "3") (pinfunction "GND_3") (pintype "bidirectional"))
      (node (ref "TF") (pin "4") (pinfunction "GND_4") (pintype "bidirectional"))
      (node (ref "TF") (pin "P6") (pinfunction "VSS_P6") (pintype "bidirectional"))
      (node (ref "U3") (pin "57") (pinfunction "GND_57") (pintype "bidirectional"))
      (node (ref "U4") (pin "4") (pinfunction "GND_4") (pintype "bidirectional"))
      (node (ref "U5") (pin "2") (pinfunction "GND_2") (pintype "bidirectional"))
      (node (ref "U7") (pin "1") (pinfunction "SDO/SA0_1") (pintype "bidirectional"))
      (node (ref "U7") (pin "6") (pinfunction "GND1_6") (pintype "bidirectional"))
      (node (ref "U7") (pin "7") (pinfunction "GND2_7") (pintype "bidirectional"))
      (node (ref "USB1") (pin "GND") (pinfunction "GND_GND") (pintype "bidirectional"))
      (node (ref "USB1") (pin "GND2") (pinfunction "GND_GND2") (pintype "bidirectional"))
      (node (ref "USB1") (pin "P$1") (pinfunction "SHLD_P$1") (pintype "bidirectional"))
      (node (ref "USB1") (pin "P$2") (pinfunction "SHLD_P$2") (pintype "bidirectional"))
      (node (ref "USB1") (pin "P$3") (pinfunction "SHLD_P$3") (pintype "bidirectional"))
      (node (ref "USB1") (pin "P$4") (pinfunction "SHLD_P$4") (pintype "bidirectional"))
      (node (ref "X1") (pin "2") (pinfunction "G2_2") (pintype "power_in"))
      (node (ref "X1") (pin "4") (pinfunction "G1_4") (pintype "power_in"))
    )
    (net (code "55") (name "Net-(ANT1-PadFEED)") (class "Default")
      (node (ref "ANT1") (pin "FEED") (pinfunction "FEED_FEED") (pintype "passive"))
      (node (ref "C18") (pin "2") (pinfunction "2_2") (pintype "passive"))
      (node (ref "L1") (pin "1") (pinfunction "1_1") (pintype "passive"))
      (node (ref "L4") (pin "2") (pinfunction "2_2") (pintype "passive"))
    )
    (net (code "56") (name "Net-(C4-Pad2)") (class "Default")
      (node (ref "C4") (pin "2") (pinfunction "2_2") (pintype "passive"))
      (node (ref "L2") (pin "2") (pinfunction "2_2") (pintype "passive"))
      (node (ref "U3") (pin "2") (pinfunction "VDD3P3_2") (pintype "bidirectional"))
      (node (ref "U3") (pin "3") (pinfunction "VDD3P3_3") (pintype "bidirectional"))
    )
    (net (code "57") (name "Net-(C8-Pad2)") (class "Default")
      (node (ref "C8") (pin "2") (pinfunction "2_2") (pintype "passive"))
      (node (ref "L4") (pin "1") (pinfunction "1_1") (pintype "passive"))
    )
    (net (code "58") (name "Net-(C42-Pad1)") (class "Default")
      (node (ref "C42") (pin "1") (pinfunction "1_1") (pintype "passive"))
      (node (ref "J1") (pin "5") (pinfunction "5_5") (pintype "bidirectional"))
    )
    (net (code "59") (name "Net-(C44-Pad1)") (class "Default")
      (node (ref "C44") (pin "1") (pinfunction "1_1") (pintype "passive"))
      (node (ref "J1") (pin "18") (pinfunction "18_18") (pintype "bidirectional"))
    )
    (net (code "60") (name "Net-(C45-Pad1)") (class "Default")
      (node (ref "C45") (pin "1") (pinfunction "1_1") (pintype "passive"))
      (node (ref "J1") (pin "19") (pinfunction "19_19") (pintype "bidirectional"))
    )
    (net (code "61") (name "Net-(C46-Pad1)") (class "Default")
      (node (ref "C46") (pin "1") (pinfunction "1_1") (pintype "passive"))
      (node (ref "J1") (pin "20") (pinfunction "20_20") (pintype "bidirectional"))
    )
    (net (code "62") (name "Net-(C47-Pad1)") (class "Default")
      (node (ref "C47") (pin "1") (pinfunction "1_1") (pintype "passive"))
      (node (ref "J1") (pin "22") (pinfunction "22_22") (pintype "bidirectional"))
    )
    (net (code "63") (name "Net-(C50-Pad1)") (class "Default")
      (node (ref "C50") (pin "1") (pinfunction "1_1") (pintype "passive"))
      (node (ref "D1") (pin "C") (pinfunction "C_C") (pintype "passive"))
      (node (ref "D4") (pin "A") (pinfunction "A_A") (pintype "passive"))
    )
    (net (code "64") (name "Net-(D3-Pad-)") (class "Default")
      (node (ref "D3") (pin "-") (pinfunction "-_-") (pintype "passive"))
      (node (ref "R5") (pin "1") (pinfunction "1_1") (pintype "passive"))
    )
    (net (code "65") (name "Net-(D5-C1)") (class "Default")
      (node (ref "D5") (pin "1") (pinfunction "C1_1") (pintype "passive"))
      (node (ref "R35") (pin "1") (pinfunction "1_1") (pintype "passive"))
      (node (ref "TF") (pin "P2") (pinfunction "CD/DAT3_P2") (pintype "bidirectional"))
    )
    (net (code "66") (name "Net-(IC2-PROG)") (class "Default")
      (node (ref "IC2") (pin "5") (pinfunction "PROG_5") (pintype "input"))
      (node (ref "R3") (pin "1") (pinfunction "1_1") (pintype "passive"))
    )
    (net (code "67") (name "Net-(IC2-STAT)") (class "Default")
      (node (ref "IC2") (pin "1") (pinfunction "STAT_1") (pintype "output"))
      (node (ref "R5") (pin "2") (pinfunction "2_2") (pintype "passive"))
    )
    (net (code "68") (name "Net-(L3-2)") (class "Default")
      (node (ref "C50") (pin "2") (pinfunction "2_2") (pintype "passive"))
      (node (ref "D6") (pin "A") (pinfunction "A_A") (pintype "passive"))
      (node (ref "L3") (pin "P$2") (pinfunction "2_P$2") (pintype "passive"))
      (node (ref "Q12") (pin "3") (pinfunction "D_3") (pintype "passive"))
    )
    (net (code "69") (name "Net-(PWR-Pad-)") (class "Default")
      (node (ref "PWR") (pin "-") (pinfunction "-_-") (pintype "passive"))
      (node (ref "R1") (pin "2") (pinfunction "2_2") (pintype "passive"))
    )
    (net (code "70") (name "Net-(TF-DAT1)") (class "Default")
      (node (ref "R10") (pin "1") (pinfunction "1_1") (pintype "passive"))
      (node (ref "TF") (pin "P8") (pinfunction "DAT1_P8") (pintype "bidirectional"))
    )
    (net (code "71") (name "Net-(TF-DAT2)") (class "Default")
      (node (ref "R8") (pin "1") (pinfunction "1_1") (pintype "passive"))
      (node (ref "TF") (pin "P1") (pinfunction "DAT2_P1") (pintype "bidirectional"))
    )
    (net (code "72") (name "Net-(U3-LNA_IN)") (class "Default")
      (node (ref "C5") (pin "2") (pinfunction "2_2") (pintype "passive"))
      (node (ref "L1") (pin "2") (pinfunction "2_2") (pintype "passive"))
      (node (ref "U3") (pin "1") (pinfunction "LNA_IN_1") (pintype "bidirectional"))
    )
    (net (code "73") (name "Net-(U3-SPICLK)") (class "Default")
      (node (ref "R18") (pin "2") (pinfunction "2_2") (pintype "passive"))
      (node (ref "U3") (pin "33") (pinfunction "SPICLK_33") (pintype "bidirectional"))
    )
    (net (code "74") (name "Net-(U3-SPID)") (class "Default")
      (node (ref "R28") (pin "2") (pinfunction "2_2") (pintype "passive"))
      (node (ref "U3") (pin "35") (pinfunction "SPID_35") (pintype "bidirectional"))
    )
    (net (code "75") (name "Net-(U3-SPIHD)") (class "Default")
      (node (ref "R25") (pin "2") (pinfunction "2_2") (pintype "passive"))
      (node (ref "U3") (pin "30") (pinfunction "SPIHD_30") (pintype "bidirectional"))
    )
    (net (code "76") (name "Net-(U3-SPIQ)") (class "Default")
      (node (ref "R16") (pin "2") (pinfunction "2_2") (pintype "passive"))
      (node (ref "U3") (pin "34") (pinfunction "SPIQ_34") (pintype "bidirectional"))
    )
    (net (code "77") (name "Net-(U3-SPIWP)") (class "Default")
      (node (ref "R23") (pin "2") (pinfunction "2_2") (pintype "passive"))
      (node (ref "U3") (pin "31") (pinfunction "SPIWP_31") (pintype "bidirectional"))
    )
    (net (code "78") (name "Net-(U3-U0TXD)") (class "Default")
      (node (ref "R12") (pin "2") (pinfunction "2_2") (pintype "passive"))
      (node (ref "U3") (pin "49") (pinfunction "U0TXD_49") (pintype "bidirectional"))
    )
    (net (code "79") (name "Net-(U3-XTAL_N)") (class "Default")
      (node (ref "C13") (pin "2") (pinfunction "2_2") (pintype "passive"))
      (node (ref "U3") (pin "53") (pinfunction "XTAL_N_53") (pintype "bidirectional"))
      (node (ref "X1") (pin "3") (pinfunction "X2_3") (pintype "bidirectional"))
    )
    (net (code "80") (name "Net-(U3-XTAL_P)") (class "Default")
      (node (ref "R34") (pin "2") (pinfunction "2_2") (pintype "passive"))
      (node (ref "U3") (pin "54") (pinfunction "XTAL_P_54") (pintype "bidirectional"))
    )
    (net (code "81") (name "Net-(U5-BYP)") (class "Default")
      (node (ref "C7") (pin "2") (pinfunction "2_2") (pintype "passive"))
      (node (ref "U5") (pin "4") (pinfunction "BYP_4") (pintype "bidirectional"))
    )
    (net (code "82") (name "Net-(USB1-CC1)") (class "Default")
      (node (ref "R32") (pin "1") (pinfunction "1_1") (pintype "passive"))
      (node (ref "USB1") (pin "A5") (pinfunction "CC1_A5") (pintype "bidirectional"))
    )
    (net (code "83") (name "Net-(USB1-CC2)") (class "Default")
      (node (ref "R31") (pin "1") (pinfunction "1_1") (pintype "passive"))
      (node (ref "USB1") (pin "B5") (pinfunction "CC2_B5") (pintype "bidirectional"))
    )
    (net (code "84") (name "Net-(X1-X1)") (class "Default")
      (node (ref "C19") (pin "1") (pinfunction "1_1") (pintype "passive"))
      (node (ref "R34") (pin "1") (pinfunction "1_1") (pintype "passive"))
      (node (ref "X1") (pin "1") (pinfunction "X1_1") (pintype "bidirectional"))
    )
    (net (code "85") (name "unconnected-(J1-Pad1)") (class "Default")
      (node (ref "J1") (pin "1") (pinfunction "1_1") (pintype "bidirectional"))
    )
    (net (code "86") (name "unconnected-(J1-Pad4)") (class "Default")
      (node (ref "J1") (pin "4") (pinfunction "4_4") (pintype "bidirectional"))
    )
    (net (code "87") (name "unconnected-(J1-Pad6)") (class "Default")
      (node (ref "J1") (pin "6") (pinfunction "6_6") (pintype "bidirectional"))
    )
    (net (code "88") (name "unconnected-(J1-Pad7)") (class "Default")
      (node (ref "J1") (pin "7") (pinfunction "7_7") (pintype "bidirectional"))
    )
    (net (code "89") (name "unconnected-(TF-SWITCH-PadG1)") (class "Default")
      (node (ref "TF") (pin "G1") (pinfunction "SWITCH_G1") (pintype "bidirectional"))
    )
    (net (code "90") (name "unconnected-(U3-GPIO33-Pad38)") (class "Default")
      (node (ref "U3") (pin "38") (pinfunction "GPIO33_38") (pintype "bidirectional"))
    )
    (net (code "91") (name "unconnected-(U3-GPIO34-Pad39)") (class "Default")
      (node (ref "U3") (pin "39") (pinfunction "GPIO34_39") (pintype "bidirectional"))
    )
    (net (code "92") (name "unconnected-(U3-GPIO35-Pad40)") (class "Default")
      (node (ref "U3") (pin "40") (pinfunction "GPIO35_40") (pintype "bidirectional"))
    )
    (net (code "93") (name "unconnected-(U3-GPIO36-Pad41)") (class "Default")
      (node (ref "U3") (pin "41") (pinfunction "GPIO36_41") (pintype "bidirectional"))
    )
    (net (code "94") (name "unconnected-(U3-GPIO37-Pad42)") (class "Default")
      (node (ref "U3") (pin "42") (pinfunction "GPIO37_42") (pintype "bidirectional"))
    )
    (net (code "95") (name "unconnected-(U7-CS-AUX-Pad10)") (class "Default")
      (node (ref "U7") (pin "10") (pinfunction "CS-AUX_10") (pintype "bidirectional"))
    )
    (net (code "96") (name "unconnected-(U7-INT2-Pad9)") (class "Default")
      (node (ref "U7") (pin "9") (pinfunction "INT2_9") (pintype "bidirectional"))
    )
    (net (code "97") (name "unconnected-(U7-SDO-AUX-Pad11)") (class "Default")
      (node (ref "U7") (pin "11") (pinfunction "SDO-AUX_11") (pintype "bidirectional"))
    )
  )
)
